# schematic.net
KiCad netlist of a schematic drawn in EasyEDA
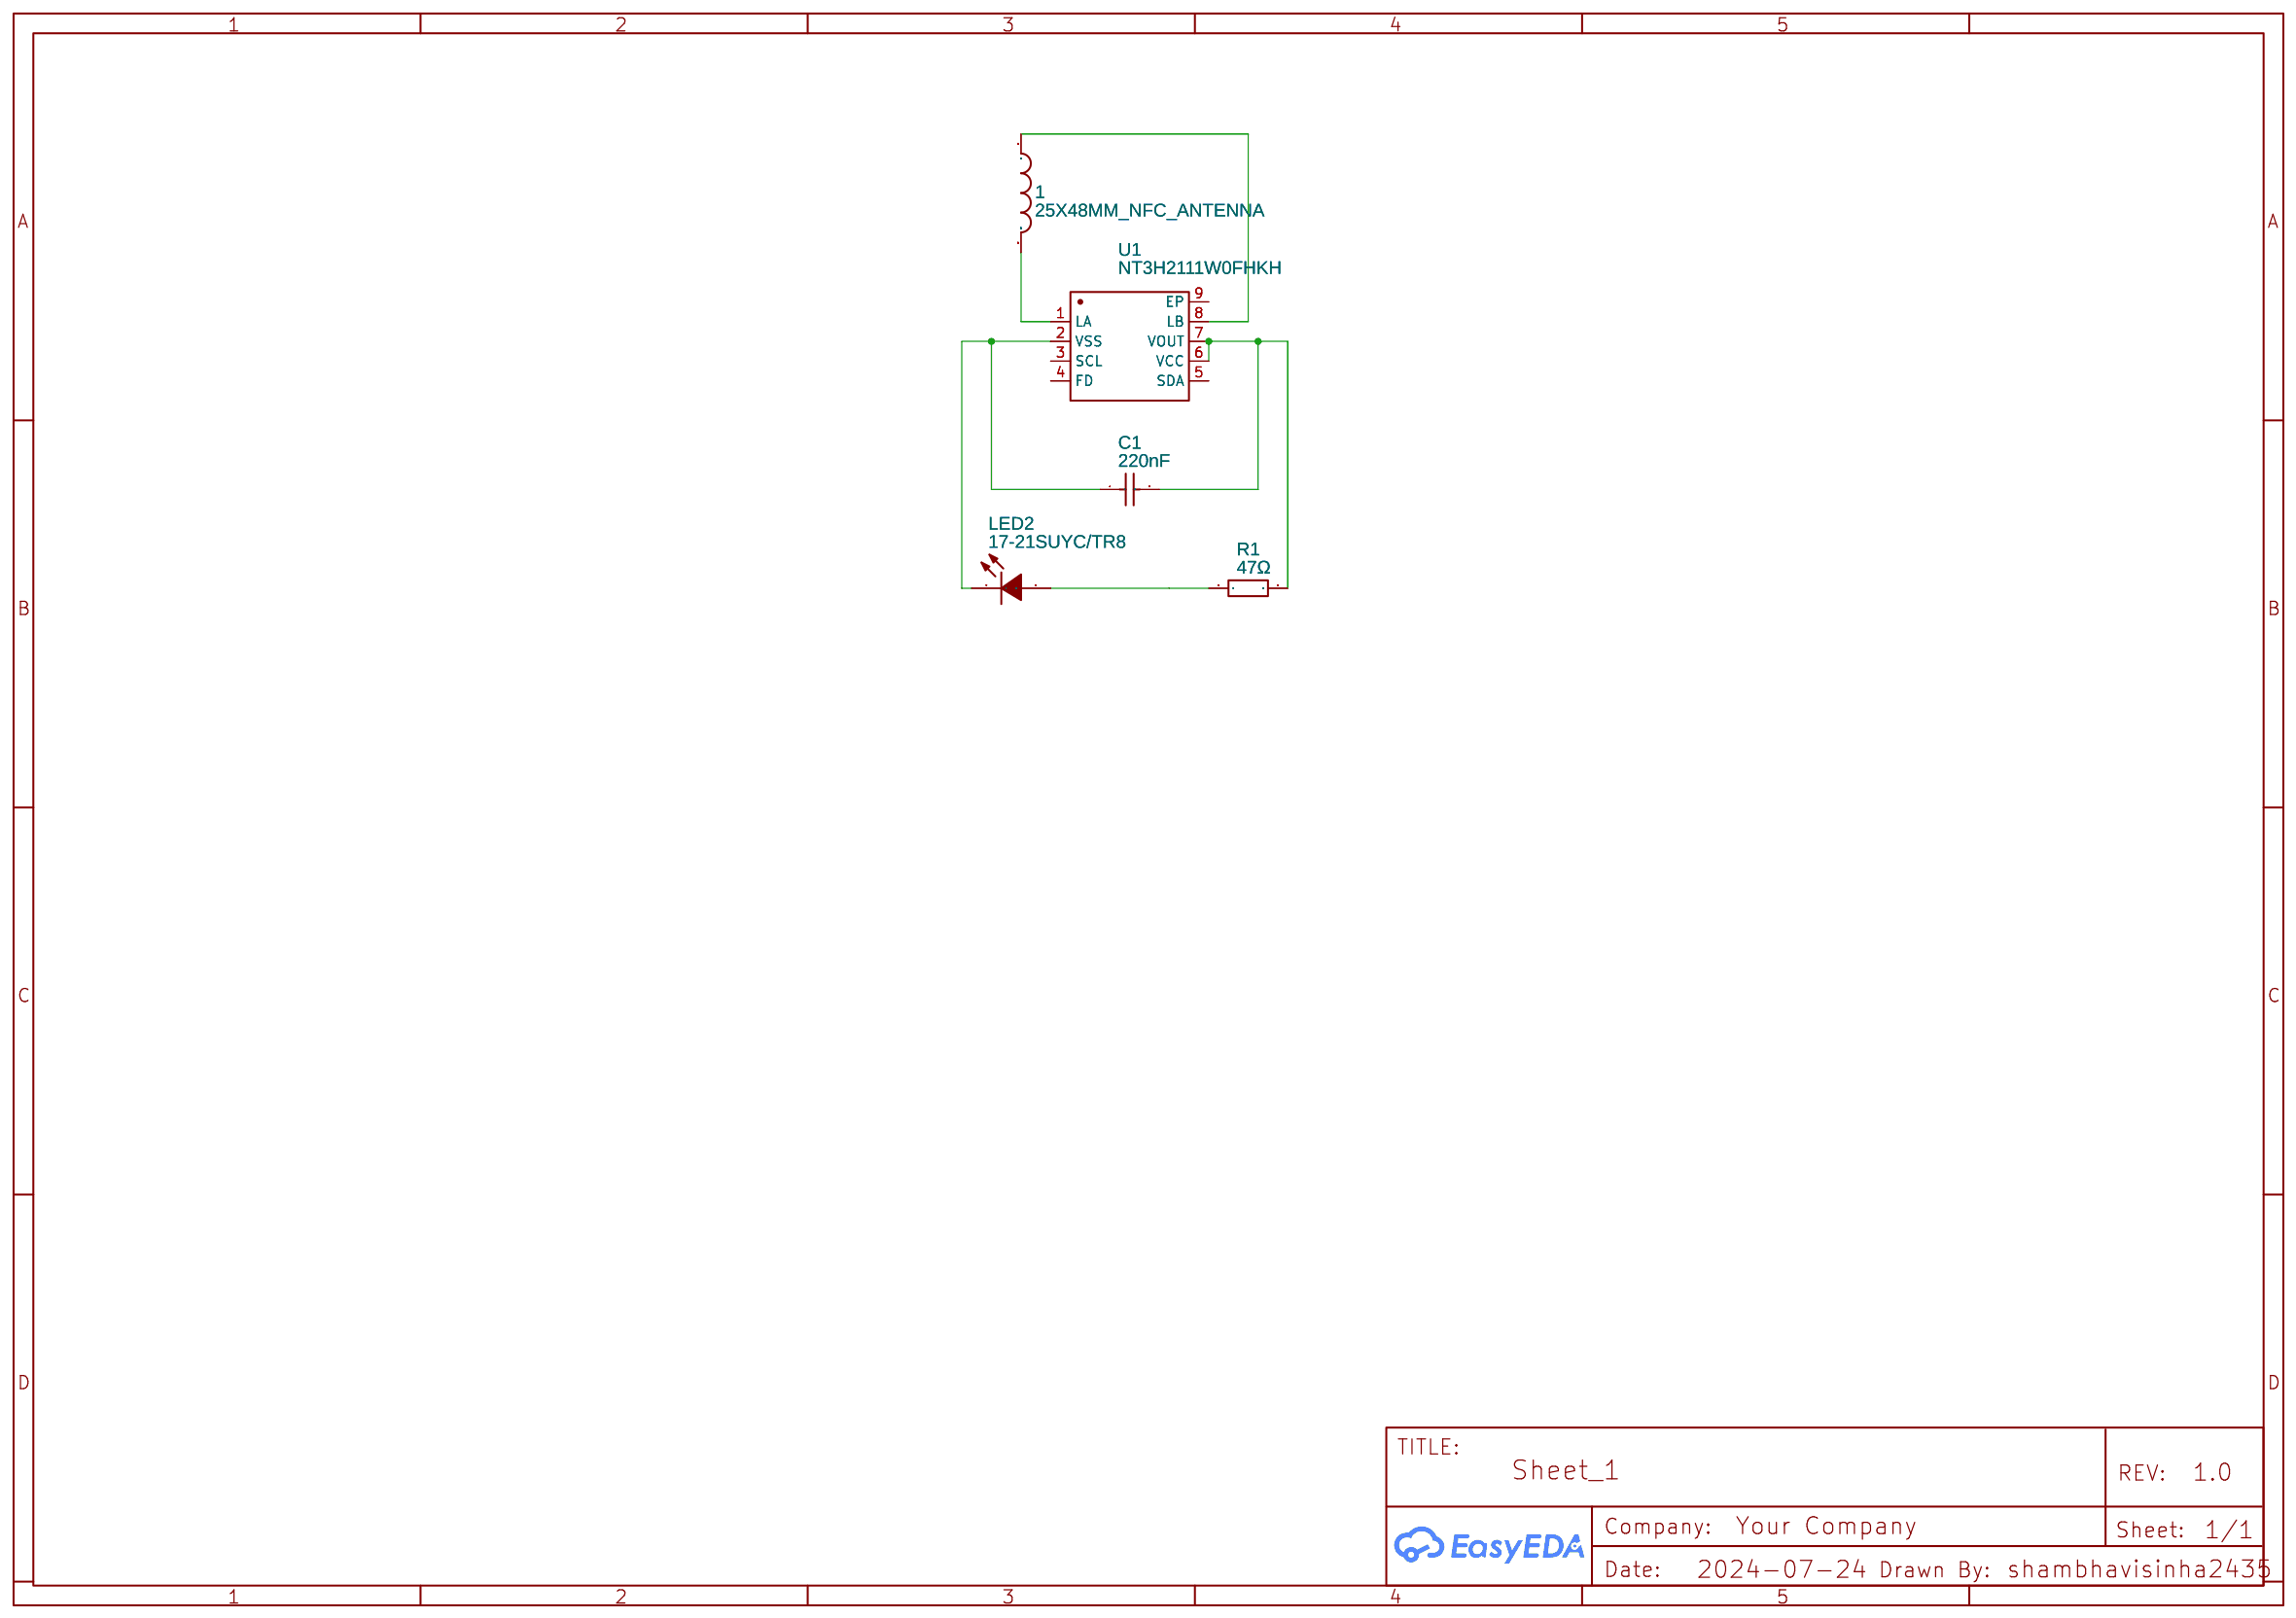
[diagram p0: schematic sheet]

(export (version "E")
  (design (tool "Eeschema 10.0.6"))
  (components
    (comp (ref "1") (value "25X48MM_NFC_ANTENNA") (libsource (lib "") (part "25X48MM_NFC_ANTENNA")))
    (comp (ref "C1")
      (value "220nF")
      (fields
        (field (name "Manufacturer Part") "CL10B224KA8NNNC")
        (field (name "Manufacturer") "SAMSUNG(三星)")
      )
      (libsource (lib "") (part "CL10B224KA8NNNC"))
    )
    (comp (ref "LED2")
      (value "17-21SUYC/TR8")
      (fields (field (name "Manufacturer Part") "KT-0805黄灯") (field (name "Manufacturer") "KENTO"))
      (libsource (lib "") (part "17-21SUYC/TR8"))
    )
    (comp (ref "R1")
      (value "47Ω")
      (fields
        (field (name "Manufacturer Part") "0603WAF470JT5E")
        (field (name "Manufacturer") "UNI-ROYAL(厚声)")
      )
      (libsource (lib "") (part "0603WAF470JT5E"))
    )
    (comp (ref "U1")
      (value "NT3H2111W0FHKH")
      (fields (field (name "Manufacturer") "NXP(恩智浦)"))
      (libsource (lib "") (part "NT3H2111W0FHKH"))
    )
  )
  (nets
    (net (code "1") (name "Net-(LED2-+)") (class "Default")
      (node (ref "LED2") (pin "1") (pinfunction "+_1") (pintype "unspecified"))
      (node (ref "R1") (pin "1") (pinfunction "1_1") (pintype "input"))
    )
    (net (code "2") (name "Net-(LED2--)") (class "Default")
      (node (ref "C1") (pin "1") (pinfunction "1_1") (pintype "input"))
      (node (ref "LED2") (pin "2") (pinfunction "-_2") (pintype "unspecified"))
      (node (ref "U1") (pin "2") (pinfunction "VSS_2") (pintype "unspecified"))
    )
    (net (code "3") (name "Net-(U1-LA)") (class "Default")
      (node (ref "1") (pin "P$2") (pinfunction "P$2_P$2") (pintype "bidirectional"))
      (node (ref "U1") (pin "1") (pinfunction "LA_1") (pintype "unspecified"))
    )
    (net (code "4") (name "Net-(U1-LB)") (class "Default")
      (node (ref "1") (pin "P$1") (pinfunction "P$1_P$1") (pintype "bidirectional"))
      (node (ref "U1") (pin "8") (pinfunction "LB_8") (pintype "unspecified"))
    )
    (net (code "5") (name "Net-(U1-VCC)") (class "Default")
      (node (ref "C1") (pin "2") (pinfunction "2_2") (pintype "input"))
      (node (ref "R1") (pin "2") (pinfunction "2_2") (pintype "input"))
      (node (ref "U1") (pin "6") (pinfunction "VCC_6") (pintype "unspecified"))
      (node (ref "U1") (pin "7") (pinfunction "VOUT_7") (pintype "unspecified"))
    )
    (net (code "6") (name "unconnected-(U1-EP-Pad9)") (class "Default")
      (node (ref "U1") (pin "9") (pinfunction "EP_9") (pintype "unspecified"))
    )
    (net (code "7") (name "unconnected-(U1-FD-Pad4)") (class "Default")
      (node (ref "U1") (pin "4") (pinfunction "FD_4") (pintype "unspecified"))
    )
    (net (code "8") (name "unconnected-(U1-SCL-Pad3)") (class "Default")
      (node (ref "U1") (pin "3") (pinfunction "SCL_3") (pintype "unspecified"))
    )
    (net (code "9") (name "unconnected-(U1-SDA-Pad5)") (class "Default")
      (node (ref "U1") (pin "5") (pinfunction "SDA_5") (pintype "unspecified"))
    )
  )
)
